# SH2_-_17V_BUCK_CONVERTER.net
KiCad netlist of a schematic drawn in Altium Designer
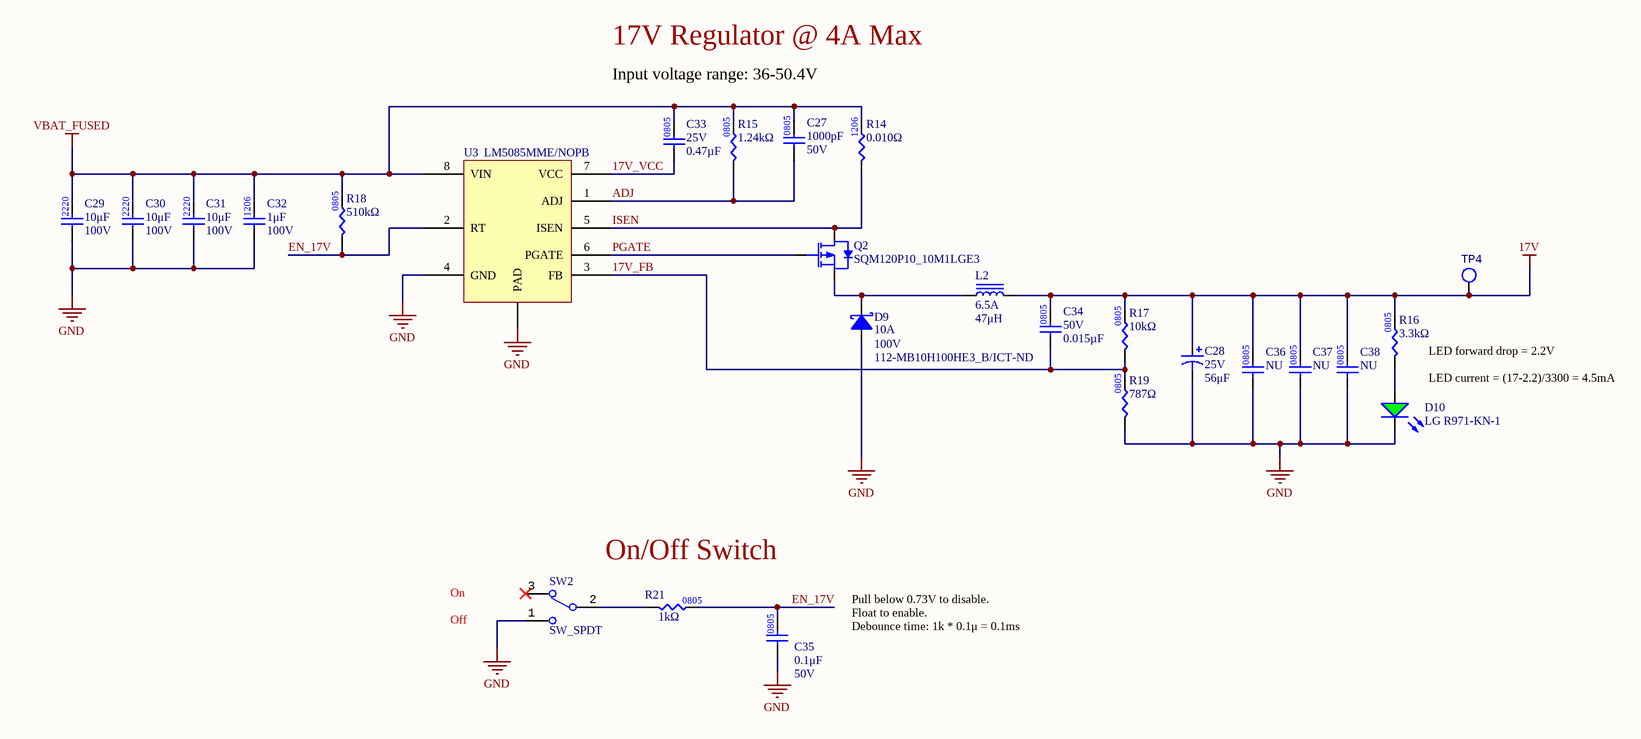
[diagram p0: SH2 - 17V BUCK CONVERTER.SchDoc]

(export (version "E")
  (design (tool "Eeschema 10.0.6"))
  (components
    (comp (ref "C27")
      (value "1000pF")
      (footprint "CAP2012")
      (description "CAP CER 1000pF 50V X7R 0805")
      (fields (field (name "VOLTAGE RATING") "50V") (field (name "Comment") "CAP_1000pF_50V_0805"))
      (libsource (lib "UWRT_Schematic_Library_2020") (part "CAP_1000pF_50V_0805"))
    )
    (comp (ref "C28")
      (value "56μF")
      (footprint "RADIAL_PANASONIC_D")
      (description "CAP ALUM POLY HYB 56UF 25V SMD")
      (fields (field (name "VOLTAGE RATING") "25V") (field (name "Comment") "CAP_56uF_25V_ALUM"))
      (libsource (lib "UWRT_Schematic_Library_2020") (part "CAP_56uF_25V_ALUM"))
    )
    (comp (ref "C29")
      (value "10μF")
      (footprint "CAP2220")
      (description "CAP CER 10UF 100V X7S 2220")
      (fields (field (name "VOLTAGE RATING") "100V") (field (name "Comment") "CAP_10μF_100V_2220"))
      (libsource (lib "UWRT_Schematic_Library_2020") (part "CAP_10μF_100V_2220"))
    )
    (comp (ref "C30")
      (value "10μF")
      (footprint "CAP2220")
      (description "CAP CER 10UF 100V X7S 2220")
      (fields (field (name "VOLTAGE RATING") "100V") (field (name "Comment") "CAP_10μF_100V_2220"))
      (libsource (lib "UWRT_Schematic_Library_2020") (part "CAP_10μF_100V_2220"))
    )
    (comp (ref "C31")
      (value "10μF")
      (footprint "CAP2220")
      (description "CAP CER 10UF 100V X7S 2220")
      (fields (field (name "VOLTAGE RATING") "100V") (field (name "Comment") "CAP_10μF_100V_2220"))
      (libsource (lib "UWRT_Schematic_Library_2020") (part "CAP_10μF_100V_2220"))
    )
    (comp (ref "C32")
      (value "1μF")
      (footprint "CAPC3216X190X50NL20T25")
      (description "CAP CER 1UF 100V X7R 1206")
      (fields (field (name "VOLTAGE RATING") "100V") (field (name "Comment") "CAP_1uF_100V_1206"))
      (libsource (lib "UWRT_Schematic_Library_2020") (part "CAP_1uF_100V_1206"))
    )
    (comp (ref "C33")
      (value "0.47µF")
      (footprint "CAP0805")
      (description "CAP CER 0.47UF 25V X5R 0805")
      (fields (field (name "VOLTAGE RATING") "25V") (field (name "Comment") "CAP_0.47uF_25V_0805"))
      (libsource (lib "UWRT_Schematic_Library_2020") (part "CAP_0.47uF_25V_0805"))
    )
    (comp (ref "C34")
      (value "0.015µF")
      (footprint "CAP0805")
      (description "CAP CER 0.015UF 50V C0G 0805")
      (fields (field (name "VOLTAGE RATING") "50V") (field (name "Comment") "CAP_0.015uF_50V_0805"))
      (libsource (lib "UWRT_Schematic_Library_2020") (part "CAP_0.015uF_50V_0805"))
    )
    (comp (ref "C35")
      (value "0.1μF")
      (footprint "CAP2012")
      (description "CAP CER 0.1UF 50V X7R 0805")
      (fields
        (field (name "VOLTAGE RATING") "50V")
        (field (name "LCSC PART #") "C49678")
        (field (name "Comment") "CAP_0.1uF_50V_0805")
      )
      (libsource (lib "UWRT_Schematic_Library_2020") (part "CAP_0.1uF_50V_0805"))
    )
    (comp (ref "C36")
      (value "NU")
      (footprint "CAP0805")
      (description "PLACEHOLDER CAPACITOR")
      (fields (field (name "Comment") "CAP_NU_0805"))
      (libsource (lib "UWRT_Schematic_Library_2020") (part "CAP_NU_0805"))
    )
    (comp (ref "C37")
      (value "NU")
      (footprint "CAP0805")
      (description "PLACEHOLDER CAPACITOR")
      (fields (field (name "Comment") "CAP_NU_0805"))
      (libsource (lib "UWRT_Schematic_Library_2020") (part "CAP_NU_0805"))
    )
    (comp (ref "C38")
      (value "NU")
      (footprint "CAP0805")
      (description "PLACEHOLDER CAPACITOR")
      (fields (field (name "Comment") "CAP_NU_0805"))
      (libsource (lib "UWRT_Schematic_Library_2020") (part "CAP_NU_0805"))
    )
    (comp (ref "D9")
      (value "DIO_SCHOTTKY_100V_5.5A")
      (footprint "D-PAK3")
      (description "DIODE SCHOTTKY 100V 10A TO263AB")
      (fields
        (field (name "VR (MAX)") "100V")
        (field (name "SUPPLIER PART NUMBER 1") "112-MB10H100HE3_B/ICT-ND")
        (field (name "FORWARD CURRENT") "10A")
      )
      (libsource (lib "UWRT_Schematic_Library_2020") (part "DIO_SCHOTTKY_100V_10A"))
    )
    (comp (ref "D10")
      (value "LED_GREEN")
      (footprint "LED_0805_GREEN")
      (description "LED GREEN DIFFUSED 0805 SMD")
      (fields (field (name "MANUFACTURER PART NUMBER 1") "LG R971-KN-1"))
      (libsource (lib "UWRT_Schematic_Library_2020") (part "LED_GREEN"))
    )
    (comp (ref "L2")
      (value "IND_47uH_6.5A")
      (footprint "IND_BOURNS_SRP1265")
      (description "FIXED IND 47UH 6.5A 90 MOHM SMD")
      (fields (field (name "CURRENT RATING") "6.5A") (field (name "INDUCTANCE") "47μH"))
      (libsource (lib "UWRT_Schematic_Library_2020") (part "IND_47uH_6.5A"))
    )
    (comp (ref "Q2")
      (value "PMOS_100V_120A")
      (footprint "D-PAK")
      (description "MOSFET P-CH 100V 120A TO263")
      (fields (field (name "MANUFACTURER PART NUMBER 1") "SQM120P10_10M1LGE3"))
      (libsource (lib "UWRT_Schematic_Library_2020") (part "PMOS_100V_120A"))
    )
    (comp (ref "R14")
      (value "0.010Ω")
      (footprint "RES1206")
      (description "RES 0.01 OHM 1% 1/2W 1206")
      (fields (field (name "Comment") "RES_0.010Ω_1206_1%"))
      (libsource (lib "UWRT_Schematic_Library_2020") (part "RES_0.010Ω_1206_1%"))
    )
    (comp (ref "R15")
      (value "1.24kΩ")
      (footprint "RES0805")
      (description "RES 1.24K OHM 1% 1/8W 0805")
      (fields (field (name "Comment") "RES_1.24kΩ_0805_1%"))
      (libsource (lib "UWRT_Schematic_Library_2020") (part "RES_1.24kΩ_0805_1%"))
    )
    (comp (ref "R16")
      (value "3.3kΩ")
      (footprint "RES0805")
      (description "RES 3.3K OHM 1% 1/8W 0805")
      (fields (field (name "LCSC PART #") "C26010") (field (name "Comment") "RES_3.3kΩ_0805_1%"))
      (libsource (lib "UWRT_Schematic_Library_2020") (part "RES_3.3kΩ_0805_1%"))
    )
    (comp (ref "R17")
      (value "10kΩ")
      (footprint "RES0805")
      (description "RES 10K OHM 5% 1/8W 0805")
      (fields (field (name "LCSC PART #") "C17414") (field (name "Comment") "RES_10kΩ_0805_5%"))
      (libsource (lib "UWRT_Schematic_Library_2020") (part "RES_10kΩ_0805_5%"))
    )
    (comp (ref "R18")
      (value "510kΩ")
      (footprint "RES0805")
      (description "RES 510K OHM 5% 1/8W 0805")
      (fields (field (name "Comment") "RES_510kΩ_0805_1%"))
      (libsource (lib "UWRT_Schematic_Library_2020") (part "RES_510kΩ_0805_1%"))
    )
    (comp (ref "R19")
      (value "787Ω")
      (footprint "RES0805")
      (description "RES 787 OHM 1% 1/8W 0805")
      (fields (field (name "Comment") "RES_787Ω_0805_1%"))
      (libsource (lib "UWRT_Schematic_Library_2020") (part "RES_787Ω_0805_1%"))
    )
    (comp (ref "R21")
      (value "1kΩ")
      (footprint "RES0805")
      (description "RES 1K OHM 1% 1/8W 0805")
      (fields (field (name "LCSC PART #") "C17513") (field (name "Comment") "RES_1kΩ_0805_1%_1"))
      (libsource (lib "UWRT_Schematic_Library_2020") (part "RES_1kΩ_0805_1%_1"))
    )
    (comp (ref "SW2")
      (value "SW_SPDT")
      (footprint "100SP1T1B4M2QE")
      (description "SWITCH TOGGLE SPDT 5A 120V")
      (libsource (lib "UWRT_Schematic_Library_2020") (part "SW_SPDT"))
    )
    (comp (ref "TP4")
      (value "TESTPOINT_LOOP")
      (footprint "TESTPOINT_LOOP")
      (description "TESTPOINT THRUHOLE")
      (libsource (lib "UWRT_Schematic_Library_2020") (part "TESTPOINT_LOOP"))
    )
    (comp (ref "U3")
      (value "BUCK_LMR14050SDDAR")
      (footprint "8-VSSOP")
      (description "IC REG CTRLR BUCK 8VSSOP")
      (fields (field (name "MANUFACTURER PART NUMBER 1") "LM5085MME/NOPB"))
      (libsource (lib "UWRT_Schematic_Library_2020") (part "BUCK_LM5085"))
    )
  )
  (nets
    (net (code "1") (name "/17V_FB") (class "Default")
      (node (ref "C34") (pin "1") (pinfunction "1_1") (pintype "passive"))
      (node (ref "R17") (pin "1") (pinfunction "1_1") (pintype "passive"))
      (node (ref "R19") (pin "2") (pinfunction "2_2") (pintype "passive"))
      (node (ref "U3") (pin "3") (pinfunction "FB_3") (pintype "passive"))
    )
    (net (code "2") (name "/17V_VCC") (class "Default")
      (node (ref "C33") (pin "1") (pinfunction "1_1") (pintype "passive"))
      (node (ref "U3") (pin "7") (pinfunction "VCC_7") (pintype "passive"))
    )
    (net (code "3") (name "/ADJ") (class "Default")
      (node (ref "C27") (pin "1") (pinfunction "1_1") (pintype "passive"))
      (node (ref "R15") (pin "1") (pinfunction "1_1") (pintype "passive"))
      (node (ref "U3") (pin "1") (pinfunction "ADJ_1") (pintype "passive"))
    )
    (net (code "4") (name "/EN_17V") (class "Default")
      (node (ref "C35") (pin "2") (pinfunction "2_2") (pintype "passive"))
      (node (ref "R18") (pin "1") (pinfunction "1_1") (pintype "passive"))
      (node (ref "R21") (pin "2") (pinfunction "2_2") (pintype "passive"))
      (node (ref "U3") (pin "2") (pinfunction "RT_2") (pintype "passive"))
    )
    (net (code "5") (name "/ISEN") (class "Default")
      (node (ref "Q2") (pin "1") (pinfunction "Drain_1") (pintype "passive"))
      (node (ref "R14") (pin "1") (pinfunction "1_1") (pintype "passive"))
      (node (ref "U3") (pin "5") (pinfunction "ISEN_5") (pintype "passive"))
    )
    (net (code "6") (name "/PGATE") (class "Default")
      (node (ref "Q2") (pin "2") (pinfunction "Gate_2") (pintype "passive"))
      (node (ref "U3") (pin "6") (pinfunction "PGATE_6") (pintype "passive"))
    )
    (net (code "7") (name "17V") (class "Default")
      (node (ref "C28") (pin "1") (pinfunction "1_1") (pintype "passive"))
      (node (ref "C34") (pin "2") (pinfunction "2_2") (pintype "passive"))
      (node (ref "C36") (pin "2") (pinfunction "2_2") (pintype "passive"))
      (node (ref "C37") (pin "2") (pinfunction "2_2") (pintype "passive"))
      (node (ref "C38") (pin "2") (pinfunction "2_2") (pintype "passive"))
      (node (ref "L2") (pin "2") (pinfunction "2_2") (pintype "passive"))
      (node (ref "R16") (pin "2") (pinfunction "2_2") (pintype "passive"))
      (node (ref "R17") (pin "2") (pinfunction "2_2") (pintype "passive"))
      (node (ref "TP4") (pin "1") (pintype "passive"))
    )
    (net (code "8") (name "GND") (class "Default")
      (node (ref "C28") (pin "2") (pinfunction "2_2") (pintype "passive"))
      (node (ref "C29") (pin "1") (pinfunction "1_1") (pintype "passive"))
      (node (ref "C30") (pin "1") (pinfunction "1_1") (pintype "passive"))
      (node (ref "C31") (pin "1") (pinfunction "1_1") (pintype "passive"))
      (node (ref "C32") (pin "1") (pinfunction "1_1") (pintype "passive"))
      (node (ref "C35") (pin "1") (pinfunction "1_1") (pintype "passive"))
      (node (ref "C36") (pin "1") (pinfunction "1_1") (pintype "passive"))
      (node (ref "C37") (pin "1") (pinfunction "1_1") (pintype "passive"))
      (node (ref "C38") (pin "1") (pinfunction "1_1") (pintype "passive"))
      (node (ref "D10") (pin "2") (pinfunction "K_2") (pintype "passive"))
      (node (ref "D9") (pin "1") (pinfunction "Anode_1") (pintype "passive"))
      (node (ref "R19") (pin "1") (pinfunction "1_1") (pintype "passive"))
      (node (ref "SW2") (pin "1") (pinfunction "1_1") (pintype "passive"))
      (node (ref "U3") (pin "4") (pinfunction "GND_4") (pintype "passive"))
      (node (ref "U3") (pin "9") (pinfunction "PAD_9") (pintype "passive"))
    )
    (net (code "9") (name "Net-(D9-Cathode)") (class "Default")
      (node (ref "D9") (pin "2") (pinfunction "Cathode_2") (pintype "passive"))
      (node (ref "L2") (pin "1") (pinfunction "1_1") (pintype "passive"))
      (node (ref "Q2") (pin "3") (pinfunction "Source_3") (pintype "passive"))
    )
    (net (code "10") (name "Net-(D10-A)") (class "Default")
      (node (ref "D10") (pin "1") (pinfunction "A_1") (pintype "passive"))
      (node (ref "R16") (pin "1") (pinfunction "1_1") (pintype "passive"))
    )
    (net (code "11") (name "Net-(R21-Pad1)") (class "Default")
      (node (ref "R21") (pin "1") (pinfunction "1_1") (pintype "passive"))
      (node (ref "SW2") (pin "2") (pinfunction "2_2") (pintype "passive"))
    )
    (net (code "12") (name "VBAT_FUSED") (class "Default")
      (node (ref "C27") (pin "2") (pinfunction "2_2") (pintype "passive"))
      (node (ref "C29") (pin "2") (pinfunction "2_2") (pintype "passive"))
      (node (ref "C30") (pin "2") (pinfunction "2_2") (pintype "passive"))
      (node (ref "C31") (pin "2") (pinfunction "2_2") (pintype "passive"))
      (node (ref "C32") (pin "2") (pinfunction "2_2") (pintype "passive"))
      (node (ref "C33") (pin "2") (pinfunction "2_2") (pintype "passive"))
      (node (ref "R14") (pin "2") (pinfunction "2_2") (pintype "passive"))
      (node (ref "R15") (pin "2") (pinfunction "2_2") (pintype "passive"))
      (node (ref "R18") (pin "2") (pinfunction "2_2") (pintype "passive"))
      (node (ref "U3") (pin "8") (pinfunction "VIN_8") (pintype "passive"))
    )
    (net (code "13") (name "unconnected-(SW2-Pad3)") (class "Default")
      (node (ref "SW2") (pin "3") (pinfunction "3_3") (pintype "passive+no_connect"))
    )
  )
)
